# 3_5mm.net
KiCad netlist of a schematic drawn in EAGLE
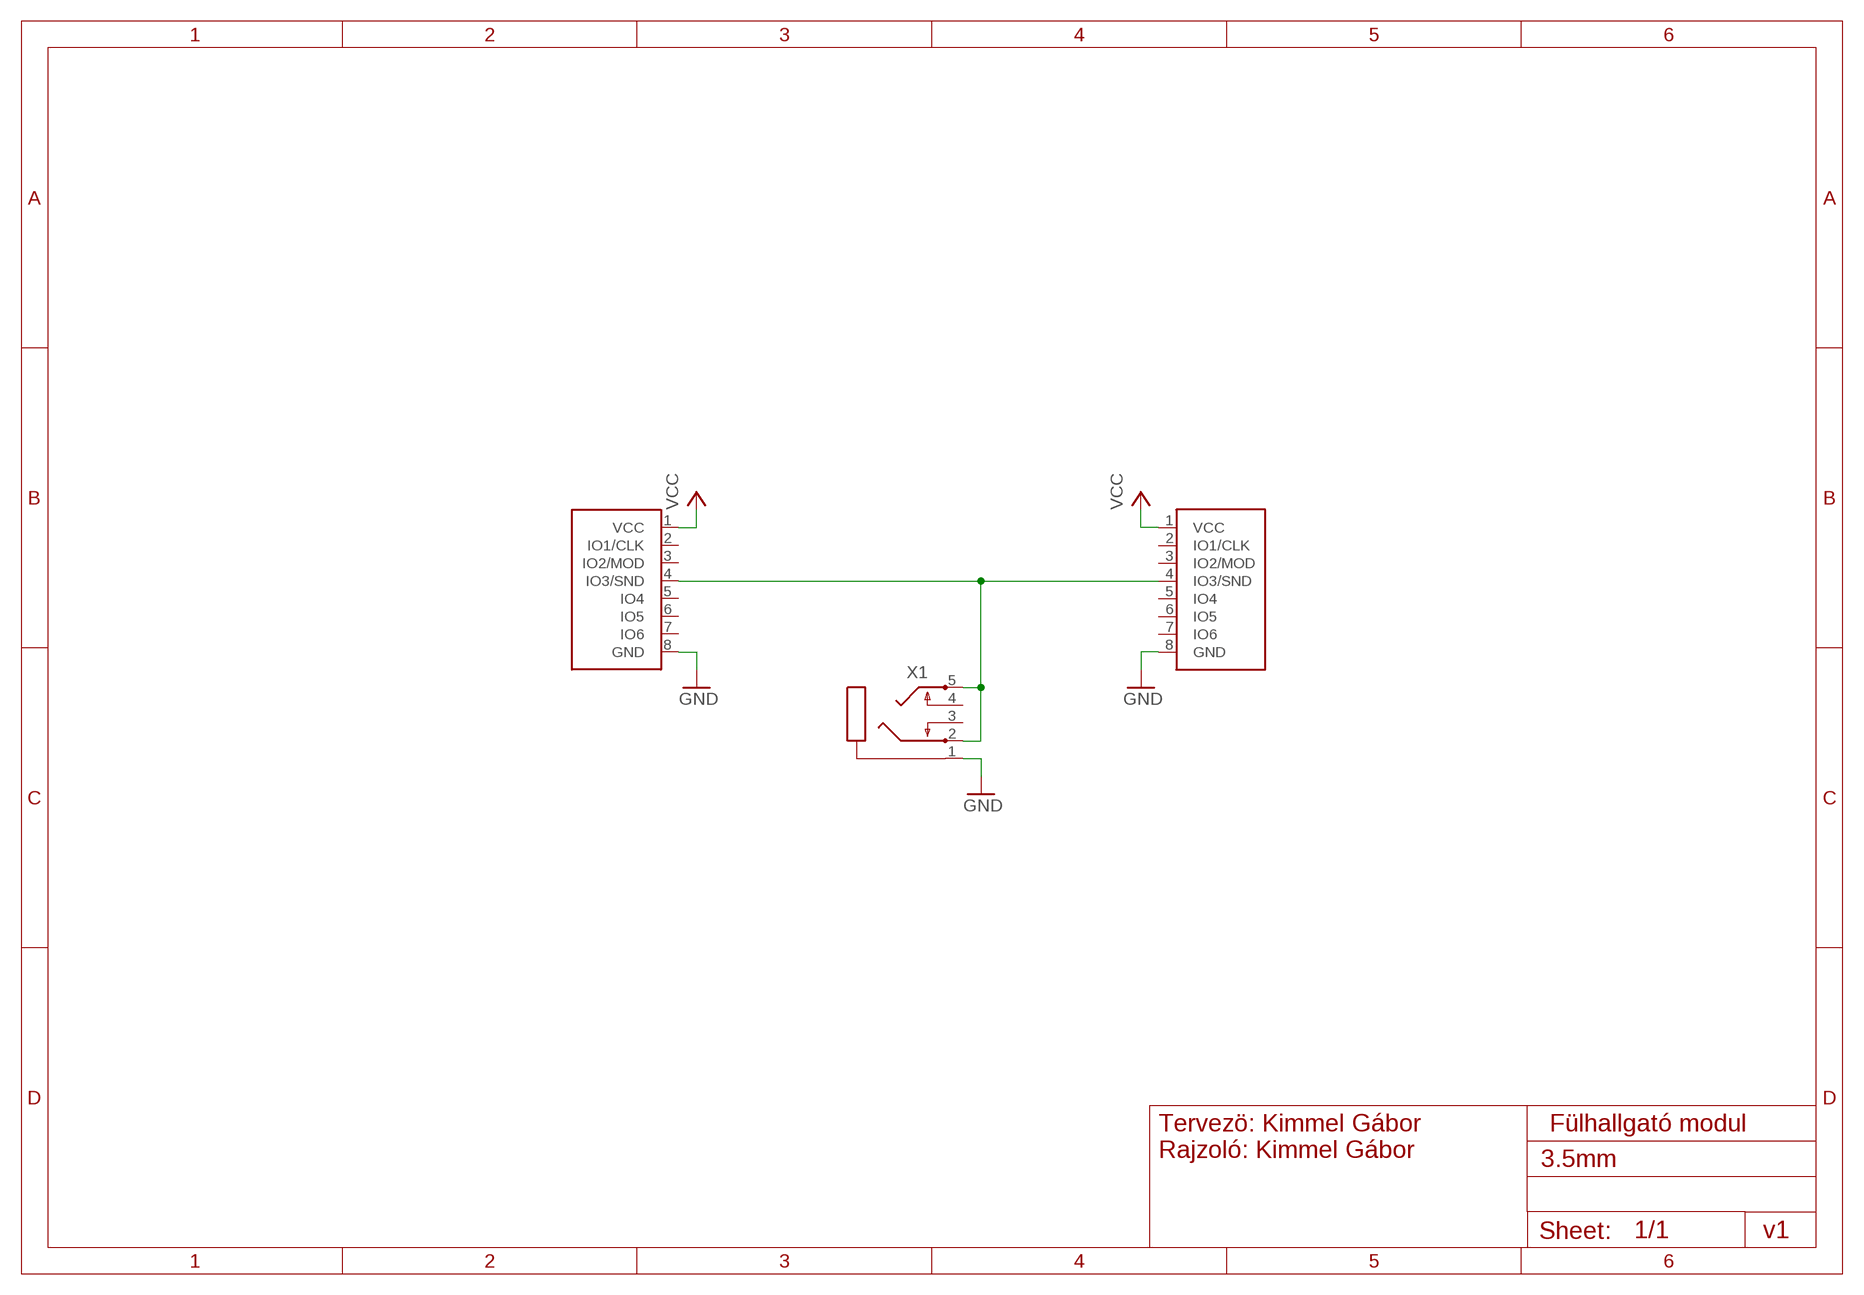
[diagram p0: schematic, sheet 1]

(export (version "E")
  (design (tool "Eeschema 10.0.6"))
  (components
    (comp (ref "U$1")
      (value "GANZ-CONNECTOR")
      (footprint "eagle-import:FE08W")
      (libsource (lib "eagle-import") (part "GANZ-CONNECTOR"))
    )
    (comp (ref "U$2")
      (value "GANZ-CONNECTOR-OUT")
      (footprint "eagle-import:MA08-1W")
      (libsource (lib "eagle-import") (part "GANZ-CONNECTOR-OUT"))
    )
    (comp (ref "X1")
      (value "PG203J")
      (footprint "eagle-import:PG203J")
      (libsource (lib "eagle-import") (part "PG203J"))
    )
  )
  (nets
    (net (code "1") (name "GND") (class "Default")
      (node (ref "U$1") (pin "8") (pinfunction "GND_8") (pintype "bidirectional"))
      (node (ref "U$2") (pin "8") (pinfunction "GND_8") (pintype "bidirectional"))
      (node (ref "X1") (pin "1") (pinfunction "1_1") (pintype "passive"))
    )
    (net (code "2") (name "Net-(U$1-IO3{slash}SND)") (class "Default")
      (node (ref "U$1") (pin "4") (pinfunction "IO3/SND_4") (pintype "bidirectional"))
      (node (ref "U$2") (pin "4") (pinfunction "IO3/SND_4") (pintype "bidirectional"))
      (node (ref "X1") (pin "2") (pinfunction "2_2") (pintype "passive"))
      (node (ref "X1") (pin "5") (pinfunction "5_5") (pintype "passive"))
    )
    (net (code "3") (name "VCC") (class "Default")
      (node (ref "U$1") (pin "1") (pinfunction "VCC_1") (pintype "bidirectional"))
      (node (ref "U$2") (pin "1") (pinfunction "VCC_1") (pintype "bidirectional"))
    )
    (net (code "4") (name "unconnected-(U$1-IO1{slash}CLK-Pad2)") (class "Default")
      (node (ref "U$1") (pin "2") (pinfunction "IO1/CLK_2") (pintype "bidirectional"))
    )
    (net (code "5") (name "unconnected-(U$1-IO2{slash}MOD-Pad3)") (class "Default")
      (node (ref "U$1") (pin "3") (pinfunction "IO2/MOD_3") (pintype "bidirectional"))
    )
    (net (code "6") (name "unconnected-(U$1-IO4-Pad5)") (class "Default")
      (node (ref "U$1") (pin "5") (pinfunction "IO4_5") (pintype "bidirectional"))
    )
    (net (code "7") (name "unconnected-(U$1-IO5-Pad6)") (class "Default")
      (node (ref "U$1") (pin "6") (pinfunction "IO5_6") (pintype "bidirectional"))
    )
    (net (code "8") (name "unconnected-(U$1-IO6-Pad7)") (class "Default")
      (node (ref "U$1") (pin "7") (pinfunction "IO6_7") (pintype "bidirectional"))
    )
    (net (code "9") (name "unconnected-(U$2-IO1{slash}CLK-Pad2)") (class "Default")
      (node (ref "U$2") (pin "2") (pinfunction "IO1/CLK_2") (pintype "bidirectional"))
    )
    (net (code "10") (name "unconnected-(U$2-IO2{slash}MOD-Pad3)") (class "Default")
      (node (ref "U$2") (pin "3") (pinfunction "IO2/MOD_3") (pintype "bidirectional"))
    )
    (net (code "11") (name "unconnected-(U$2-IO4-Pad5)") (class "Default")
      (node (ref "U$2") (pin "5") (pinfunction "IO4_5") (pintype "bidirectional"))
    )
    (net (code "12") (name "unconnected-(U$2-IO5-Pad6)") (class "Default")
      (node (ref "U$2") (pin "6") (pinfunction "IO5_6") (pintype "bidirectional"))
    )
    (net (code "13") (name "unconnected-(U$2-IO6-Pad7)") (class "Default")
      (node (ref "U$2") (pin "7") (pinfunction "IO6_7") (pintype "bidirectional"))
    )
    (net (code "14") (name "unconnected-(X1-Pad3)") (class "Default")
      (node (ref "X1") (pin "3") (pinfunction "3_3") (pintype "passive"))
    )
    (net (code "15") (name "unconnected-(X1-Pad4)") (class "Default")
      (node (ref "X1") (pin "4") (pinfunction "4_4") (pintype "passive"))
    )
  )
)
